# SCHEMATIC_BUCK_OFFICIAL.net
KiCad netlist of a schematic drawn in Altium Designer
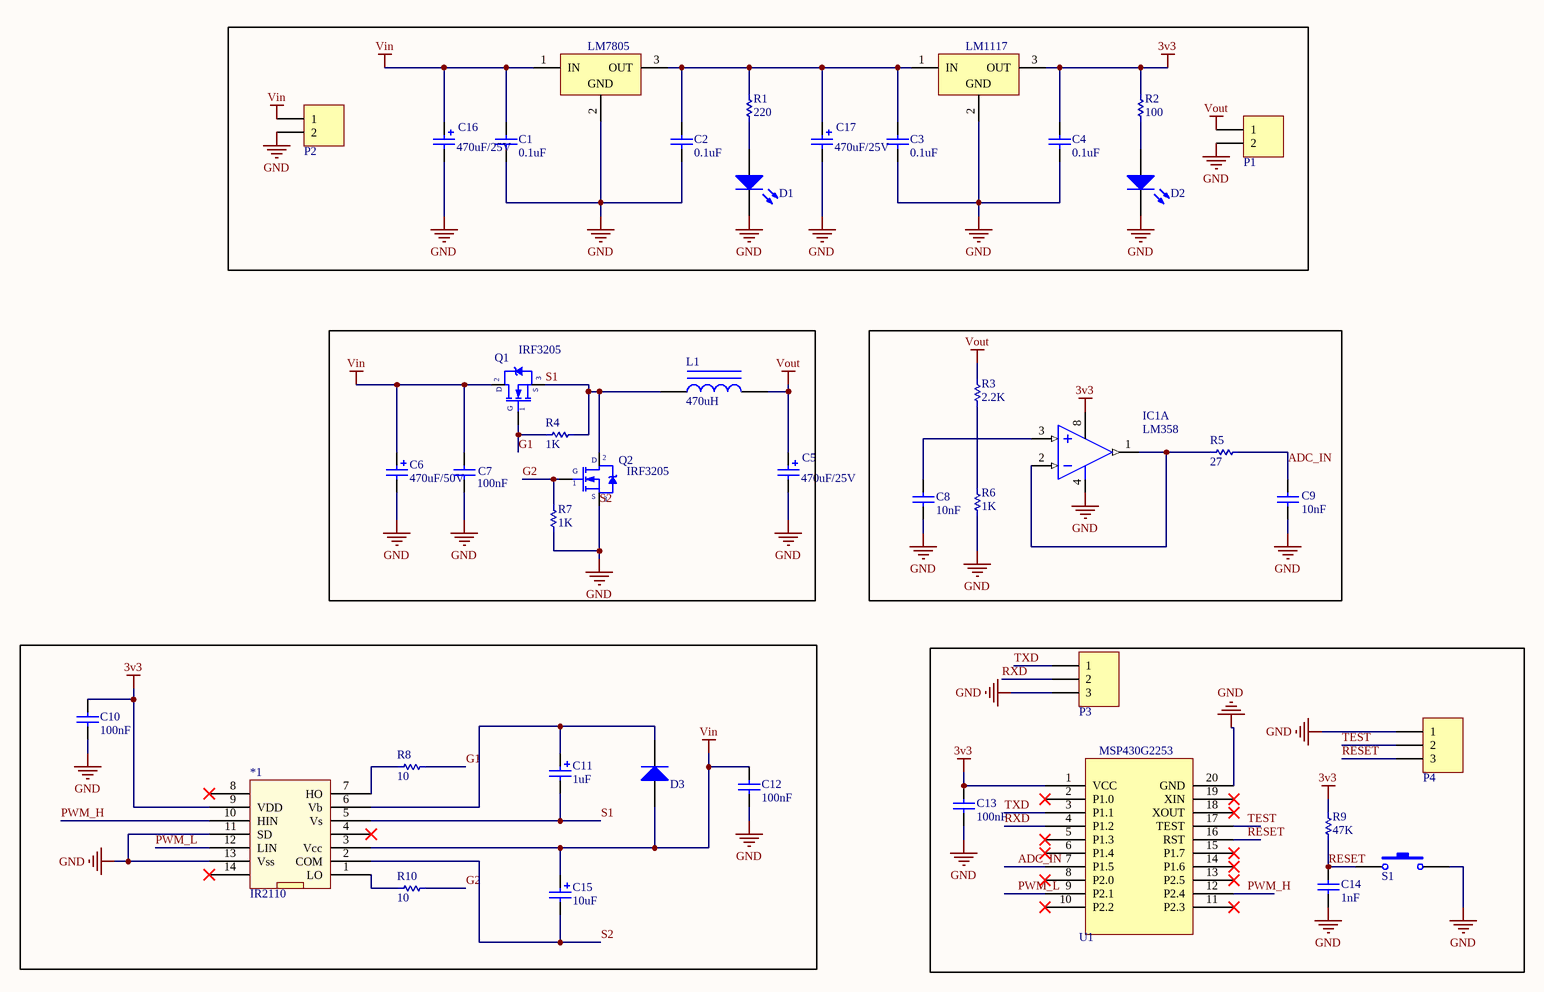
[diagram p0: SCHEMATIC_BUCK_OFFICIAL.SchDoc]

(export (version "E")
  (design (tool "Eeschema 10.0.6"))
  (components
    (comp (ref "*1") (value "IR2110") (footprint "IR_2110_2") (libsource (lib "ir2110") (part "IR2110")))
    (comp (ref "C1")
      (value "0.1uF")
      (footprint "CN1")
      (description "Capacitor")
      (fields (field (name "Comment") "Cap Non-Pol"))
      (libsource (lib "PIF_Library") (part "Cap Non-Pol"))
    )
    (comp (ref "C2")
      (value "0.1uF")
      (footprint "CN1")
      (description "Capacitor")
      (fields (field (name "Comment") "Cap Non-Pol"))
      (libsource (lib "PIF_Library") (part "Cap Non-Pol"))
    )
    (comp (ref "C3")
      (value "0.1uF")
      (footprint "CN1")
      (description "Capacitor")
      (fields (field (name "Comment") "Cap Non-Pol"))
      (libsource (lib "PIF_Library") (part "Cap Non-Pol"))
    )
    (comp (ref "C4")
      (value "0.1uF")
      (footprint "CN1")
      (description "Capacitor")
      (fields (field (name "Comment") "Cap Non-Pol"))
      (libsource (lib "PIF_Library") (part "Cap Non-Pol"))
    )
    (comp (ref "C5")
      (value "470uF/25V")
      (footprint "CP1/2")
      (description "Polarized Capacitor (Radial)")
      (fields (field (name "Comment") "Cap Pol"))
      (libsource (lib "PIF_Library") (part "Cap Pol"))
    )
    (comp (ref "C6")
      (value "470uF/50V")
      (footprint "CP1.5/3.4")
      (description "Polarized Capacitor (Radial)")
      (fields (field (name "Comment") "Cap Pol"))
      (libsource (lib "PIF_Library") (part "Cap Pol"))
    )
    (comp (ref "C7")
      (value "100nF")
      (footprint "CN1")
      (description "Capacitor")
      (fields (field (name "Comment") "Cap Non-Pol"))
      (libsource (lib "PIF_Library") (part "Cap Non-Pol"))
    )
    (comp (ref "C8")
      (value "10nF")
      (footprint "CN1")
      (description "Capacitor")
      (fields (field (name "Comment") "Cap Non-Pol"))
      (libsource (lib "PIF_Library") (part "Cap Non-Pol"))
    )
    (comp (ref "C9")
      (value "10nF")
      (footprint "CN1")
      (description "Capacitor")
      (fields (field (name "Comment") "Cap Non-Pol"))
      (libsource (lib "PIF_Library") (part "Cap Non-Pol"))
    )
    (comp (ref "C10")
      (value "100nF")
      (footprint "CN1")
      (description "Capacitor")
      (fields (field (name "Comment") "Cap Non-Pol"))
      (libsource (lib "PIF_Library") (part "Cap Non-Pol"))
    )
    (comp (ref "C11")
      (value "1uF")
      (footprint "CP1/2")
      (description "Polarized Capacitor (Radial)")
      (fields (field (name "Comment") "Cap Pol"))
      (libsource (lib "PIF_Library") (part "Cap Pol"))
    )
    (comp (ref "C12")
      (value "100nF")
      (footprint "CN1")
      (description "Capacitor")
      (fields (field (name "Comment") "Cap Non-Pol"))
      (libsource (lib "PIF_Library") (part "Cap Non-Pol"))
    )
    (comp (ref "C13")
      (value "100nF")
      (footprint "CN1")
      (description "Capacitor")
      (fields (field (name "Comment") "Cap Non-Pol"))
      (libsource (lib "PIF_Library") (part "Cap Non-Pol"))
    )
    (comp (ref "C14")
      (value "1nF")
      (footprint "CN1")
      (description "Capacitor")
      (fields (field (name "Comment") "Cap Non-Pol"))
      (libsource (lib "PIF_Library") (part "Cap Non-Pol"))
    )
    (comp (ref "C15")
      (value "10uF")
      (footprint "CP1/2")
      (description "Polarized Capacitor (Radial)")
      (fields (field (name "Comment") "Cap Pol"))
      (libsource (lib "PIF_Library") (part "Cap Pol"))
    )
    (comp (ref "C16")
      (value "470uF/25V")
      (footprint "CP1/2")
      (description "Polarized Capacitor (Radial)")
      (fields (field (name "Comment") "Cap Pol"))
      (libsource (lib "PIF_Library") (part "Cap Pol"))
    )
    (comp (ref "C17")
      (value "470uF/25V")
      (footprint "CP1/2")
      (description "Polarized Capacitor (Radial)")
      (fields (field (name "Comment") "Cap Pol"))
      (libsource (lib "PIF_Library") (part "Cap Pol"))
    )
    (comp (ref "D1") (value "LED") (footprint "LED-3mm") (libsource (lib "PIF_Library") (part "LED")))
    (comp (ref "D2") (value "LED") (footprint "LED-3mm") (libsource (lib "PIF_Library") (part "LED")))
    (comp (ref "D3")
      (value "Diode")
      (footprint "D1A")
      (description "Default Diode")
      (libsource (lib "PIF_Library") (part "Diode"))
    )
    (comp (ref "IC1")
      (value "LM358")
      (footprint "DIP8/W0.3")
      (description "Low-Power Dual Operational Amplifier")
      (libsource (lib "syhaunguyen") (part "LM358"))
    )
    (comp (ref "L1")
      (value "470uH")
      (footprint "R1/2W")
      (description "Magnetic-Core Inductor")
      (fields (field (name "MANUFACTURER") "Generic Components") (field (name "Comment") "Inductor Iron"))
      (libsource (lib "syhaunguyen") (part "Inductor Iron"))
    )
    (comp (ref "LM1117")
      (value "LM7805")
      (footprint "QTO-220")
      (description "Positive Voltage Regulator")
      (libsource (lib "PIF_Library") (part "LM7805"))
    )
    (comp (ref "LM7805")
      (value "LM7805")
      (footprint "QTO-220")
      (description "Positive Voltage Regulator")
      (libsource (lib "PIF_Library") (part "LM7805"))
    )
    (comp (ref "P1")
      (value "Domino 2")
      (footprint "DOMINO 2- 5mm")
      (description "Domino, 2-Pin")
      (fields (field (name "PUBLISHER") "Altium Limited"))
      (libsource (lib "PIF_Library") (part "Domino 2"))
    )
    (comp (ref "P2")
      (value "Domino 2")
      (footprint "DOMINO 2- 5mm")
      (description "Domino, 2-Pin")
      (fields (field (name "PUBLISHER") "Altium Limited"))
      (libsource (lib "PIF_Library") (part "Domino 2"))
    )
    (comp (ref "P3")
      (value "Header 3")
      (footprint "JP3")
      (description "Header, 3-Pin")
      (fields (field (name "PUBLISHER") "Altium Limited"))
      (libsource (lib "PIF_Library") (part "Header 3"))
    )
    (comp (ref "P4")
      (value "Header 3")
      (footprint "JP3")
      (description "Header, 3-Pin")
      (fields (field (name "PUBLISHER") "Altium Limited"))
      (libsource (lib "PIF_Library") (part "Header 3"))
    )
    (comp (ref "Q1")
      (value "IRF3205")
      (footprint "QTO-220")
      (description "MOSFET N - CHANNEL 500V - 0.75 - 8A - TO-220")
      (libsource (lib "syhaunguyen") (part "IRF840"))
    )
    (comp (ref "Q2")
      (value "IRF3205")
      (footprint "QTO-220")
      (description "MOSFET N - CHANNEL 500V - 0.75 - 8A - TO-220")
      (libsource (lib "syhaunguyen") (part "IRF840"))
    )
    (comp (ref "R1")
      (value "220")
      (footprint "RES-SM-0805")
      (fields (field (name "Comment") "Resistor 1/4W"))
      (libsource (lib "PIF_C16_2_lib") (part "RES"))
    )
    (comp (ref "R2")
      (value "100")
      (footprint "RES-SM-0805")
      (fields (field (name "Comment") "Resistor 1/4W"))
      (libsource (lib "PIF_C16_2_lib") (part "RES"))
    )
    (comp (ref "R3")
      (value "2.2K")
      (footprint "RES-SM-0805")
      (fields (field (name "Comment") "Resistor 1/4W"))
      (libsource (lib "PIF_C16_2_lib") (part "RES"))
    )
    (comp (ref "R4")
      (value "1K")
      (footprint "RES-SM-0805")
      (fields (field (name "Comment") "Resistor 1/4W"))
      (libsource (lib "PIF_C16_2_lib") (part "RES"))
    )
    (comp (ref "R5")
      (value "27")
      (footprint "RES-SM-0805")
      (fields (field (name "Comment") "Resistor 1/4W"))
      (libsource (lib "PIF_C16_2_lib") (part "RES"))
    )
    (comp (ref "R6")
      (value "1K")
      (footprint "RES-SM-0805")
      (fields (field (name "Comment") "Resistor 1/4W"))
      (libsource (lib "PIF_C16_2_lib") (part "RES"))
    )
    (comp (ref "R7")
      (value "1K")
      (footprint "RES-SM-0805")
      (fields (field (name "Comment") "Resistor 1/4W"))
      (libsource (lib "PIF_C16_2_lib") (part "RES"))
    )
    (comp (ref "R8")
      (value "10")
      (footprint "RES-SM-0805")
      (fields (field (name "Comment") "Resistor 1/4W"))
      (libsource (lib "PIF_C16_2_lib") (part "RES"))
    )
    (comp (ref "R9")
      (value "47K")
      (footprint "RES-SM-0805")
      (fields (field (name "Comment") "Resistor 1/4W"))
      (libsource (lib "PIF_C16_2_lib") (part "RES"))
    )
    (comp (ref "R10")
      (value "10")
      (footprint "RES-SM-0805")
      (fields (field (name "Comment") "Resistor 1/4W"))
      (libsource (lib "PIF_C16_2_lib") (part "RES"))
    )
    (comp (ref "S1")
      (value "Tact SW - 2Pin")
      (footprint "SW2")
      (description "Switch button 2 pin")
      (libsource (lib "PIF_Library") (part "Tact SW - 2Pin"))
    )
    (comp (ref "U1")
      (value "MSP430G2553")
      (footprint "DIP20/W0.3")
      (libsource (lib "PIF_Library") (part "MSP430G2553"))
    )
  )
  (nets
    (net (code "1") (name "/ADC_IN") (class "Default")
      (node (ref "C9") (pin "1") (pinfunction "1_1") (pintype "passive"))
      (node (ref "R5") (pin "2") (pintype "passive"))
      (node (ref "U1") (pin "7") (pinfunction "P1.5_7") (pintype "passive"))
    )
    (net (code "2") (name "/G1") (class "Default")
      (node (ref "Q1") (pin "1") (pinfunction "G_1") (pintype "passive"))
      (node (ref "R4") (pin "1") (pintype "passive"))
      (node (ref "R8") (pin "1") (pintype "passive"))
    )
    (net (code "3") (name "/G2") (class "Default")
      (node (ref "Q2") (pin "1") (pinfunction "G_1") (pintype "passive"))
      (node (ref "R10") (pin "1") (pintype "passive"))
      (node (ref "R7") (pin "2") (pintype "passive"))
    )
    (net (code "4") (name "/PWM_H") (class "Default")
      (node (ref "*1") (pin "10") (pinfunction "HIN_10") (pintype "passive"))
      (node (ref "U1") (pin "12") (pinfunction "P2.4_12") (pintype "passive"))
    )
    (net (code "5") (name "/PWM_L") (class "Default")
      (node (ref "*1") (pin "12") (pinfunction "LIN_12") (pintype "passive"))
      (node (ref "U1") (pin "9") (pinfunction "P2.1_9") (pintype "passive"))
    )
    (net (code "6") (name "/RESET") (class "Default")
      (node (ref "C14") (pin "2") (pinfunction "2_2") (pintype "passive"))
      (node (ref "P4") (pin "3") (pinfunction "3_3") (pintype "passive"))
      (node (ref "R9") (pin "1") (pintype "passive"))
      (node (ref "S1") (pin "1") (pinfunction "1_1") (pintype "passive"))
      (node (ref "U1") (pin "16") (pinfunction "RST_16") (pintype "passive"))
    )
    (net (code "7") (name "/RXD") (class "Default")
      (node (ref "P3") (pin "2") (pinfunction "2_2") (pintype "passive"))
      (node (ref "U1") (pin "4") (pinfunction "P1.2_4") (pintype "passive"))
    )
    (net (code "8") (name "/S1") (class "Default")
      (node (ref "*1") (pin "5") (pinfunction "Vs_5") (pintype "passive"))
      (node (ref "C11") (pin "2") (pinfunction "2_2") (pintype "passive"))
      (node (ref "L1") (pin "1") (pinfunction "1_1") (pintype "passive"))
      (node (ref "Q1") (pin "3") (pinfunction "S_3") (pintype "passive"))
      (node (ref "Q2") (pin "2") (pinfunction "D_2") (pintype "passive"))
      (node (ref "R4") (pin "2") (pintype "passive"))
    )
    (net (code "9") (name "/TEST") (class "Default")
      (node (ref "P4") (pin "2") (pinfunction "2_2") (pintype "passive"))
      (node (ref "U1") (pin "17") (pinfunction "TEST_17") (pintype "passive"))
    )
    (net (code "10") (name "/TXD") (class "Default")
      (node (ref "P3") (pin "1") (pinfunction "1_1") (pintype "passive"))
      (node (ref "U1") (pin "3") (pinfunction "P1.1_3") (pintype "passive"))
    )
    (net (code "11") (name "3v3") (class "Default")
      (node (ref "*1") (pin "9") (pinfunction "VDD_9") (pintype "passive"))
      (node (ref "C10") (pin "2") (pinfunction "2_2") (pintype "passive"))
      (node (ref "C13") (pin "2") (pinfunction "2_2") (pintype "passive"))
      (node (ref "C4") (pin "2") (pinfunction "2_2") (pintype "passive"))
      (node (ref "IC1") (pin "8") (pinfunction "+V_8") (pintype "passive"))
      (node (ref "LM1117") (pin "3") (pinfunction "OUT_3") (pintype "power_in"))
      (node (ref "R2") (pin "2") (pintype "passive"))
      (node (ref "R9") (pin "2") (pintype "passive"))
      (node (ref "U1") (pin "1") (pinfunction "VCC_1") (pintype "passive"))
    )
    (net (code "12") (name "GND") (class "Default")
      (node (ref "*1") (pin "11") (pinfunction "SD_11") (pintype "passive"))
      (node (ref "*1") (pin "13") (pinfunction "Vss_13") (pintype "passive"))
      (node (ref "*1") (pin "2") (pinfunction "COM_2") (pintype "passive"))
      (node (ref "C1") (pin "1") (pinfunction "1_1") (pintype "passive"))
      (node (ref "C10") (pin "1") (pinfunction "1_1") (pintype "passive"))
      (node (ref "C12") (pin "1") (pinfunction "1_1") (pintype "passive"))
      (node (ref "C13") (pin "1") (pinfunction "1_1") (pintype "passive"))
      (node (ref "C14") (pin "1") (pinfunction "1_1") (pintype "passive"))
      (node (ref "C15") (pin "2") (pinfunction "2_2") (pintype "passive"))
      (node (ref "C16") (pin "2") (pinfunction "2_2") (pintype "passive"))
      (node (ref "C17") (pin "2") (pinfunction "2_2") (pintype "passive"))
      (node (ref "C2") (pin "1") (pinfunction "1_1") (pintype "passive"))
      (node (ref "C3") (pin "1") (pinfunction "1_1") (pintype "passive"))
      (node (ref "C4") (pin "1") (pinfunction "1_1") (pintype "passive"))
      (node (ref "C5") (pin "2") (pinfunction "2_2") (pintype "passive"))
      (node (ref "C6") (pin "2") (pinfunction "2_2") (pintype "passive"))
      (node (ref "C7") (pin "1") (pinfunction "1_1") (pintype "passive"))
      (node (ref "C8") (pin "1") (pinfunction "1_1") (pintype "passive"))
      (node (ref "C9") (pin "2") (pinfunction "2_2") (pintype "passive"))
      (node (ref "D1") (pin "2") (pinfunction "K_2") (pintype "passive"))
      (node (ref "D2") (pin "2") (pinfunction "K_2") (pintype "passive"))
      (node (ref "IC1") (pin "4") (pinfunction "-V_4") (pintype "passive"))
      (node (ref "LM1117") (pin "2") (pinfunction "GND_2") (pintype "power_in"))
      (node (ref "LM7805") (pin "2") (pinfunction "GND_2") (pintype "power_in"))
      (node (ref "P1") (pin "2") (pinfunction "2_2") (pintype "passive"))
      (node (ref "P2") (pin "2") (pinfunction "2_2") (pintype "passive"))
      (node (ref "P3") (pin "3") (pinfunction "3_3") (pintype "passive"))
      (node (ref "P4") (pin "1") (pinfunction "1_1") (pintype "passive"))
      (node (ref "Q2") (pin "3") (pinfunction "S_3") (pintype "passive"))
      (node (ref "R6") (pin "1") (pintype "passive"))
      (node (ref "R7") (pin "1") (pintype "passive"))
      (node (ref "S1") (pin "2") (pinfunction "2_2") (pintype "passive"))
      (node (ref "U1") (pin "20") (pinfunction "GND_20") (pintype "passive"))
    )
    (net (code "13") (name "Net-(*1-HO)") (class "Default")
      (node (ref "*1") (pin "7") (pinfunction "HO_7") (pintype "passive"))
      (node (ref "R8") (pin "2") (pintype "passive"))
    )
    (net (code "14") (name "Net-(*1-LO)") (class "Default")
      (node (ref "*1") (pin "1") (pinfunction "LO_1") (pintype "passive"))
      (node (ref "R10") (pin "2") (pintype "passive"))
    )
    (net (code "15") (name "Net-(*1-Vb)") (class "Default")
      (node (ref "*1") (pin "6") (pinfunction "Vb_6") (pintype "passive"))
      (node (ref "C11") (pin "1") (pinfunction "1_1") (pintype "passive"))
      (node (ref "D3") (pin "2") (pinfunction "K_2") (pintype "passive"))
    )
    (net (code "16") (name "Net-(D1-A)") (class "Default")
      (node (ref "D1") (pin "1") (pinfunction "A_1") (pintype "passive"))
      (node (ref "R1") (pin "1") (pintype "passive"))
    )
    (net (code "17") (name "Net-(D2-A)") (class "Default")
      (node (ref "D2") (pin "1") (pinfunction "A_1") (pintype "passive"))
      (node (ref "R2") (pin "1") (pintype "passive"))
    )
    (net (code "18") (name "Net-(IC1A-IN+)") (class "Default")
      (node (ref "C8") (pin "2") (pinfunction "2_2") (pintype "passive"))
      (node (ref "IC1") (pin "3") (pinfunction "IN+_3") (pintype "input"))
    )
    (net (code "19") (name "Net-(IC1A-IN-)") (class "Default")
      (node (ref "IC1") (pin "1") (pinfunction "OUT_1") (pintype "output"))
      (node (ref "IC1") (pin "2") (pinfunction "IN-_2") (pintype "input"))
      (node (ref "R5") (pin "1") (pintype "passive"))
    )
    (net (code "20") (name "Net-(LM1117-IN)") (class "Default")
      (node (ref "C17") (pin "1") (pinfunction "1_1") (pintype "passive"))
      (node (ref "C2") (pin "2") (pinfunction "2_2") (pintype "passive"))
      (node (ref "C3") (pin "2") (pinfunction "2_2") (pintype "passive"))
      (node (ref "LM1117") (pin "1") (pinfunction "IN_1") (pintype "power_in"))
      (node (ref "LM7805") (pin "3") (pinfunction "OUT_3") (pintype "power_in"))
      (node (ref "R1") (pin "2") (pintype "passive"))
    )
    (net (code "21") (name "Net-(R3-Pad1)") (class "Default")
      (node (ref "R3") (pin "1") (pintype "passive"))
      (node (ref "R6") (pin "2") (pintype "passive"))
    )
    (net (code "22") (name "Vin") (class "Default")
      (node (ref "*1") (pin "3") (pinfunction "Vcc_3") (pintype "passive"))
      (node (ref "C1") (pin "2") (pinfunction "2_2") (pintype "passive"))
      (node (ref "C12") (pin "2") (pinfunction "2_2") (pintype "passive"))
      (node (ref "C15") (pin "1") (pinfunction "1_1") (pintype "passive"))
      (node (ref "C16") (pin "1") (pinfunction "1_1") (pintype "passive"))
      (node (ref "C6") (pin "1") (pinfunction "1_1") (pintype "passive"))
      (node (ref "C7") (pin "2") (pinfunction "2_2") (pintype "passive"))
      (node (ref "D3") (pin "1") (pinfunction "A_1") (pintype "passive"))
      (node (ref "LM7805") (pin "1") (pinfunction "IN_1") (pintype "power_in"))
      (node (ref "P2") (pin "1") (pinfunction "1_1") (pintype "passive"))
      (node (ref "Q1") (pin "2") (pinfunction "D_2") (pintype "passive"))
    )
    (net (code "23") (name "Vout") (class "Default")
      (node (ref "C5") (pin "1") (pinfunction "1_1") (pintype "passive"))
      (node (ref "L1") (pin "2") (pinfunction "2_2") (pintype "passive"))
      (node (ref "P1") (pin "1") (pinfunction "1_1") (pintype "passive"))
      (node (ref "R3") (pin "2") (pintype "passive"))
    )
    (net (code "24") (name "unconnected-(*1-Pad4)") (class "Default")
      (node (ref "*1") (pin "4") (pintype "passive+no_connect"))
    )
    (net (code "25") (name "unconnected-(*1-Pad8)") (class "Default")
      (node (ref "*1") (pin "8") (pintype "passive+no_connect"))
    )
    (net (code "26") (name "unconnected-(*1-Pad14)") (class "Default")
      (node (ref "*1") (pin "14") (pintype "passive+no_connect"))
    )
    (net (code "27") (name "unconnected-(U1-P1.0-Pad2)") (class "Default")
      (node (ref "U1") (pin "2") (pinfunction "P1.0_2") (pintype "passive+no_connect"))
    )
    (net (code "28") (name "unconnected-(U1-P1.3-Pad5)") (class "Default")
      (node (ref "U1") (pin "5") (pinfunction "P1.3_5") (pintype "passive+no_connect"))
    )
    (net (code "29") (name "unconnected-(U1-P1.4-Pad6)") (class "Default")
      (node (ref "U1") (pin "6") (pinfunction "P1.4_6") (pintype "passive+no_connect"))
    )
    (net (code "30") (name "unconnected-(U1-P1.6-Pad14)") (class "Default")
      (node (ref "U1") (pin "14") (pinfunction "P1.6_14") (pintype "passive+no_connect"))
    )
    (net (code "31") (name "unconnected-(U1-P1.7-Pad15)") (class "Default")
      (node (ref "U1") (pin "15") (pinfunction "P1.7_15") (pintype "passive+no_connect"))
    )
    (net (code "32") (name "unconnected-(U1-P2.0-Pad8)") (class "Default")
      (node (ref "U1") (pin "8") (pinfunction "P2.0_8") (pintype "passive+no_connect"))
    )
    (net (code "33") (name "unconnected-(U1-P2.2-Pad10)") (class "Default")
      (node (ref "U1") (pin "10") (pinfunction "P2.2_10") (pintype "passive+no_connect"))
    )
    (net (code "34") (name "unconnected-(U1-P2.3-Pad11)") (class "Default")
      (node (ref "U1") (pin "11") (pinfunction "P2.3_11") (pintype "passive+no_connect"))
    )
    (net (code "35") (name "unconnected-(U1-P2.5-Pad13)") (class "Default")
      (node (ref "U1") (pin "13") (pinfunction "P2.5_13") (pintype "passive+no_connect"))
    )
    (net (code "36") (name "unconnected-(U1-XIN-Pad19)") (class "Default")
      (node (ref "U1") (pin "19") (pinfunction "XIN_19") (pintype "passive+no_connect"))
    )
    (net (code "37") (name "unconnected-(U1-XOUT-Pad18)") (class "Default")
      (node (ref "U1") (pin "18") (pinfunction "XOUT_18") (pintype "passive+no_connect"))
    )
  )
)
